# CAN_Transceiver_Breakout_Board.net
KiCad netlist of a schematic drawn in Altium Designer
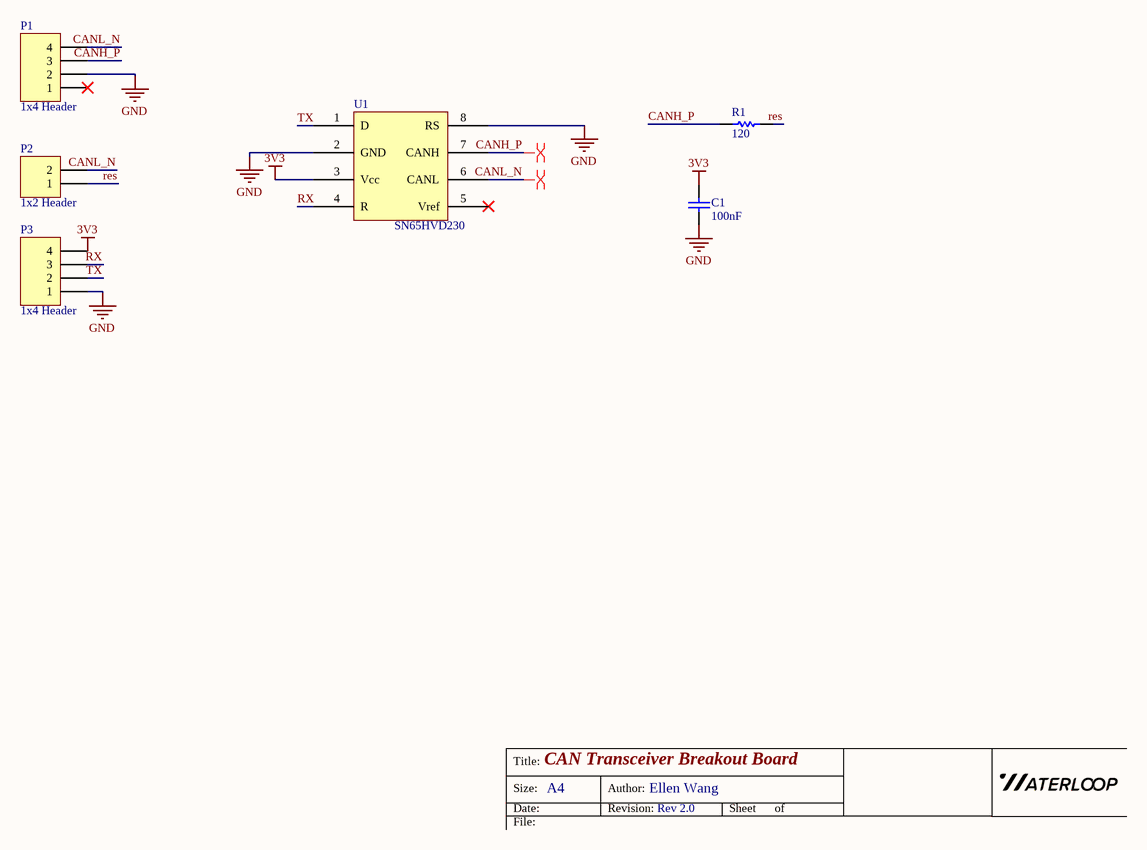
[diagram p0: CAN_Transceiver Breakout Board .SchDoc]

(export (version "E")
  (design (tool "Eeschema 10.0.6"))
  (components
    (comp (ref "C1")
      (value "100nF")
      (footprint "0805 - Capacitor")
      (description "Nonpolarized Capacitor")
      (fields
        (field (name "MANUFACTURER") "YAGEO")
        (field (name "MANUFACTURER PART NUMBER") "CC0805KPX7R9BB104")
      )
      (libsource (lib "General") (part "Capacitor - Nonpolarized"))
    )
    (comp (ref "P1")
      (value "1x4 Header")
      (footprint "HDR1X4")
      (description "1x4 Pin Header")
      (libsource (lib "GeneralConnectors") (part "1x4 Header"))
    )
    (comp (ref "P2")
      (value "1x2 Header")
      (footprint "HDR1X2")
      (description "1x2 Pin Header")
      (libsource (lib "GeneralConnectors") (part "1x2 Header"))
    )
    (comp (ref "P3")
      (value "1x4 Header")
      (footprint "HDR1X4")
      (description "1x4 Pin Header")
      (libsource (lib "GeneralConnectors") (part "1x4 Header"))
    )
    (comp (ref "R1")
      (value "120")
      (footprint "0603 - Resistor")
      (description "Resistor")
      (fields
        (field (name "MANUFACTURER PART NUMBER") "RC0603FR-10120RL")
        (field (name "MANUFACTURER") "YAGEO")
      )
      (libsource (lib "General") (part "Resistor"))
    )
    (comp (ref "U1")
      (value "SN65HVD230")
      (footprint "SN65HVD230")
      (description "3.3V CAN Transeiver with standby")
      (libsource (lib "General") (part "SN65HVD230"))
    )
  )
  (nets
    (net (code "1") (name "/CANH_P") (class "Default")
      (node (ref "P1") (pin "3") (pinfunction "3_3") (pintype "passive"))
      (node (ref "R1") (pin "1") (pinfunction "1_1") (pintype "passive"))
      (node (ref "U1") (pin "7") (pinfunction "CANH_7") (pintype "passive"))
    )
    (net (code "2") (name "/CANL_N") (class "Default")
      (node (ref "P1") (pin "4") (pinfunction "4_4") (pintype "passive"))
      (node (ref "P2") (pin "2") (pinfunction "2_2") (pintype "passive"))
      (node (ref "U1") (pin "6") (pinfunction "CANL_6") (pintype "passive"))
    )
    (net (code "3") (name "/RX") (class "Default")
      (node (ref "P3") (pin "3") (pinfunction "3_3") (pintype "passive"))
      (node (ref "U1") (pin "4") (pinfunction "R_4") (pintype "passive"))
    )
    (net (code "4") (name "/TX") (class "Default")
      (node (ref "P3") (pin "2") (pinfunction "2_2") (pintype "passive"))
      (node (ref "U1") (pin "1") (pinfunction "D_1") (pintype "passive"))
    )
    (net (code "5") (name "/res") (class "Default")
      (node (ref "P2") (pin "1") (pinfunction "1_1") (pintype "passive"))
      (node (ref "R1") (pin "2") (pinfunction "2_2") (pintype "passive"))
    )
    (net (code "6") (name "3V3") (class "Default")
      (node (ref "C1") (pin "2") (pinfunction "2_2") (pintype "passive"))
      (node (ref "P3") (pin "4") (pinfunction "4_4") (pintype "passive"))
      (node (ref "U1") (pin "3") (pinfunction "Vcc_3") (pintype "passive"))
    )
    (net (code "7") (name "GND") (class "Default")
      (node (ref "C1") (pin "1") (pinfunction "1_1") (pintype "passive"))
      (node (ref "P1") (pin "2") (pinfunction "2_2") (pintype "passive"))
      (node (ref "P3") (pin "1") (pinfunction "1_1") (pintype "passive"))
      (node (ref "U1") (pin "2") (pinfunction "GND_2") (pintype "passive"))
      (node (ref "U1") (pin "8") (pinfunction "RS_8") (pintype "passive"))
    )
    (net (code "8") (name "unconnected-(P1-Pad1)") (class "Default")
      (node (ref "P1") (pin "1") (pinfunction "1_1") (pintype "passive+no_connect"))
    )
    (net (code "9") (name "unconnected-(U1-Vref-Pad5)") (class "Default")
      (node (ref "U1") (pin "5") (pinfunction "Vref_5") (pintype "passive+no_connect"))
    )
  )
)
